# Power.net
KiCad netlist of a schematic drawn in Altium Designer
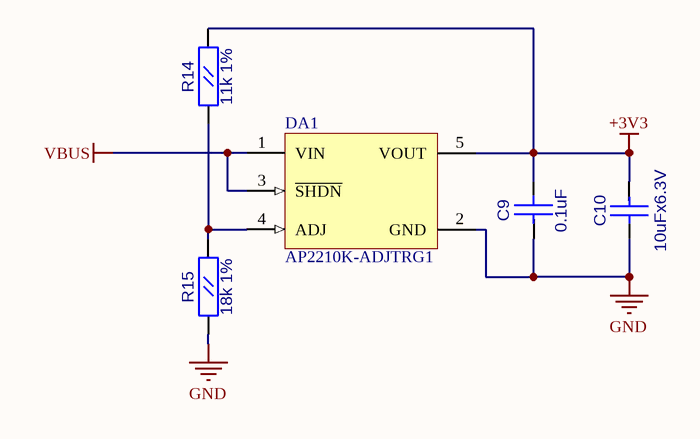
[diagram p0: Power.SchDoc]

(export (version "E")
  (design (tool "Eeschema 10.0.6"))
  (components
    (comp (ref "C9")
      (value "0.1uF")
      (footprint "CC0603")
      (description "CC0603")
      (libsource (lib "gprs_modem_2") (part "CC0603"))
    )
    (comp (ref "C10")
      (value "10uFx6.3V")
      (footprint "CC0805")
      (description "CC0805")
      (libsource (lib "gprs_modem_2") (part "CC0805"))
    )
    (comp (ref "DA1")
      (value "AP2210K-ADJTRG1")
      (footprint "SOT23-5")
      (fields (field (name "PUBLISHER") "Altium Limited"))
      (libsource (lib "gprs_modem_2") (part "MCP1824T-ADJE/OT"))
    )
    (comp (ref "R14")
      (value "11k 1%")
      (footprint "RC0603")
      (description "RC0603")
      (libsource (lib "gprs_modem_2") (part "RC0603"))
    )
    (comp (ref "R15")
      (value "18k 1%")
      (footprint "RC0603")
      (description "RC0603")
      (libsource (lib "gprs_modem_2") (part "RC0603"))
    )
  )
  (nets
    (net (code "1") (name "+3V3") (class "Default")
      (node (ref "C10") (pin "2") (pinfunction "B_2") (pintype "passive"))
      (node (ref "C9") (pin "1") (pinfunction "A_1") (pintype "passive"))
      (node (ref "DA1") (pin "5") (pinfunction "VOUT_5") (pintype "power_in"))
      (node (ref "R14") (pin "2") (pinfunction "B_2") (pintype "passive"))
    )
    (net (code "2") (name "GND") (class "Default")
      (node (ref "C10") (pin "1") (pinfunction "A_1") (pintype "passive"))
      (node (ref "C9") (pin "2") (pinfunction "B_2") (pintype "passive"))
      (node (ref "DA1") (pin "2") (pinfunction "GND_2") (pintype "power_in"))
      (node (ref "R15") (pin "1") (pinfunction "A_1") (pintype "passive"))
    )
    (net (code "3") (name "Net-(DA1-ADJ)") (class "Default")
      (node (ref "DA1") (pin "4") (pinfunction "ADJ_4") (pintype "input"))
      (node (ref "R14") (pin "1") (pinfunction "A_1") (pintype "passive"))
      (node (ref "R15") (pin "2") (pinfunction "B_2") (pintype "passive"))
    )
    (net (code "4") (name "VBUS") (class "Default")
      (node (ref "DA1") (pin "1") (pinfunction "VIN_1") (pintype "power_in"))
      (node (ref "DA1") (pin "3") (pinfunction "~{SHDN}_3") (pintype "input"))
    )
  )
)
